# WiFi_Turntable_Controller_v2.net
KiCad netlist of a schematic drawn in EAGLE
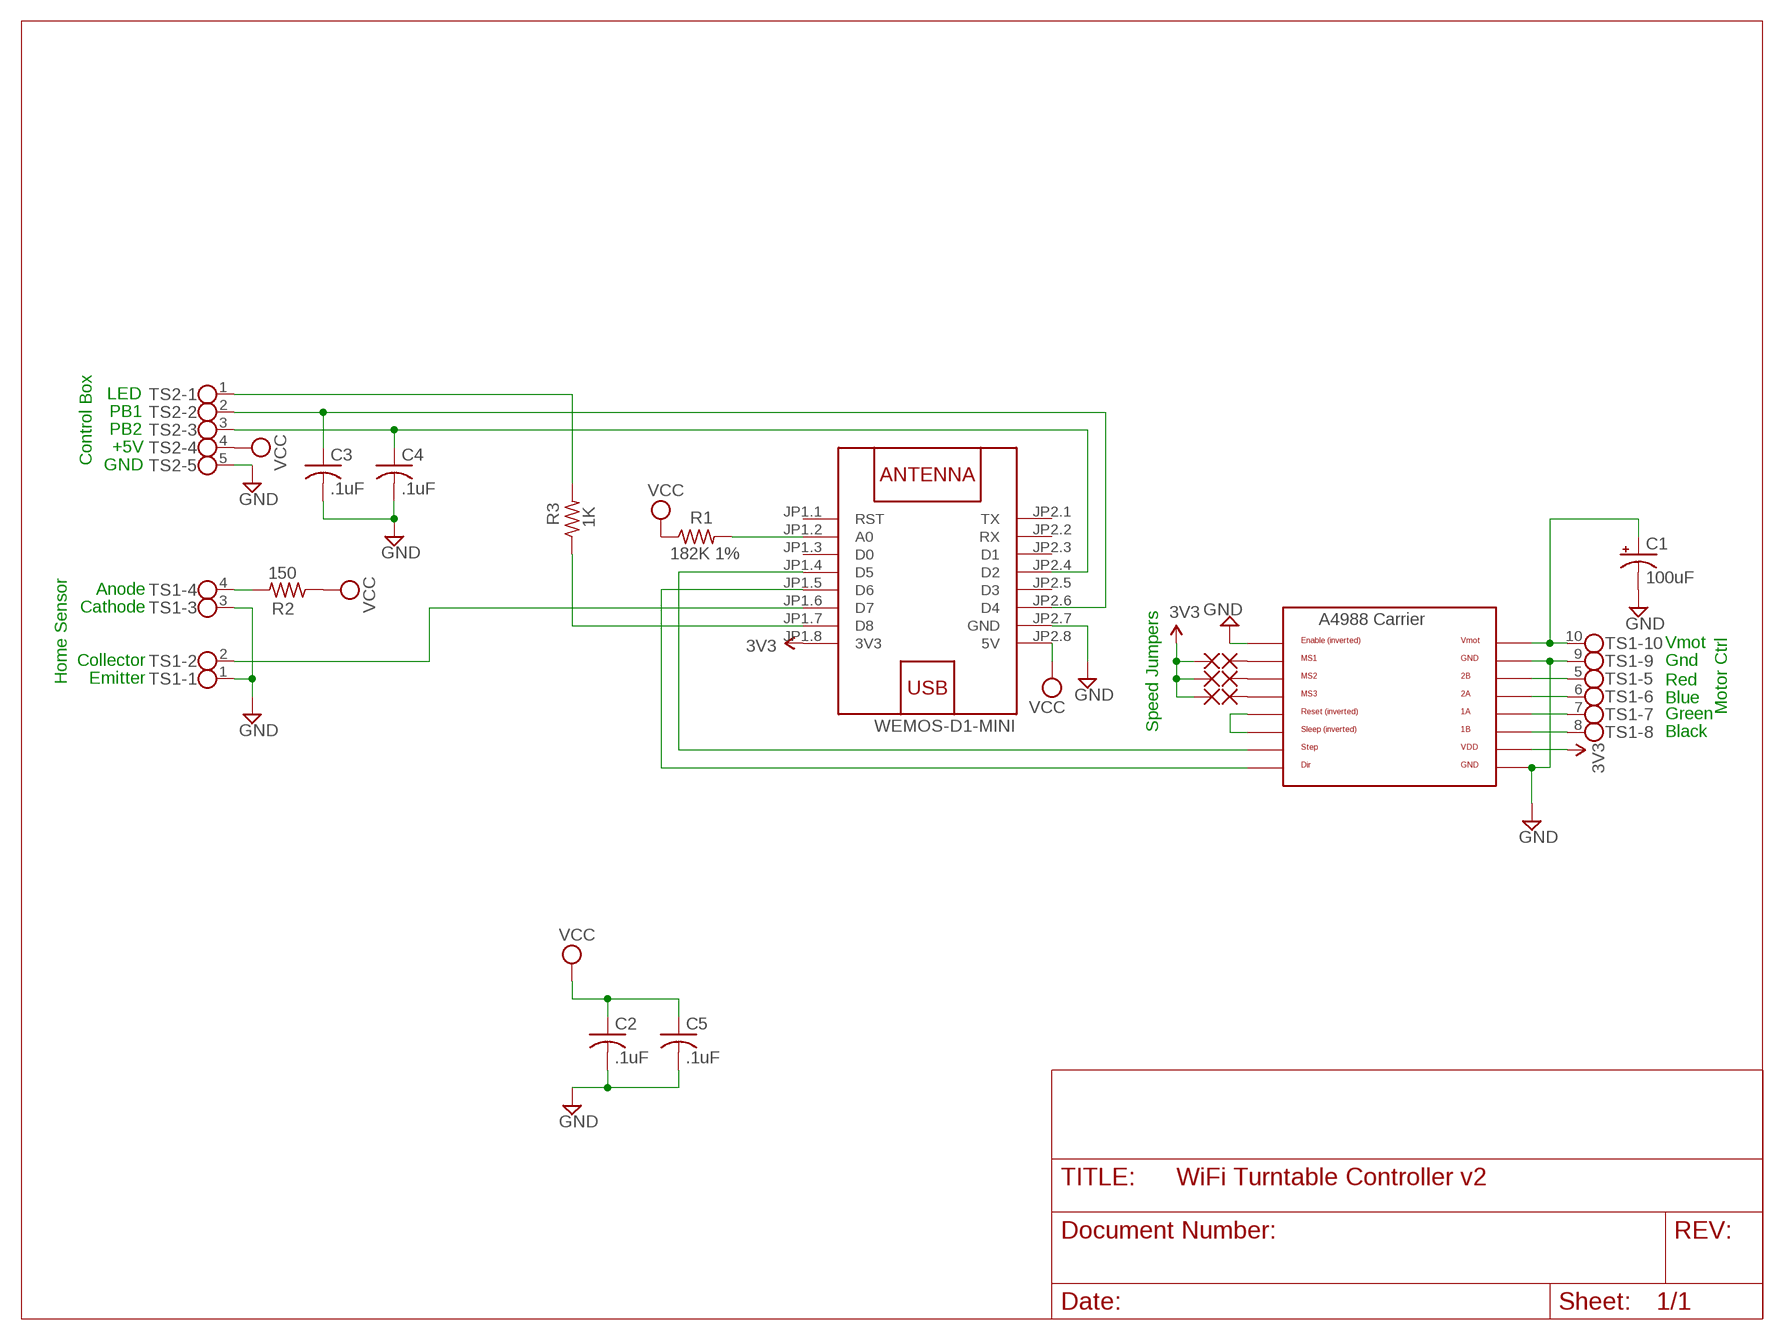
[diagram p0: schematic, sheet 1]

(export (version "E")
  (design (tool "Eeschema 10.0.6"))
  (components
    (comp (ref "C1")
      (value "100uF")
      (footprint "eagle-import:E3,5-8")
      (libsource (lib "eagle-import") (part "CPOL-USE3.5-8"))
    )
    (comp (ref "C2")
      (value ".1uF")
      (footprint "eagle-import:C1206")
      (libsource (lib "eagle-import") (part "C-USC1206"))
    )
    (comp (ref "C3")
      (value ".1uF")
      (footprint "eagle-import:C1206")
      (libsource (lib "eagle-import") (part "C-USC1206"))
    )
    (comp (ref "C4")
      (value ".1uF")
      (footprint "eagle-import:C1206")
      (libsource (lib "eagle-import") (part "C-USC1206"))
    )
    (comp (ref "C5")
      (value ".1uF")
      (footprint "eagle-import:C1206")
      (libsource (lib "eagle-import") (part "C-USC1206"))
    )
    (comp (ref "PAD1")
      (value "1,6/0,8")
      (footprint "eagle-import:1,6_0,8")
      (libsource (lib "eagle-import") (part "1,6/0,8"))
    )
    (comp (ref "PAD2")
      (value "1,6/0,8")
      (footprint "eagle-import:1,6_0,8")
      (libsource (lib "eagle-import") (part "1,6/0,8"))
    )
    (comp (ref "PAD3")
      (value "1,6/0,8")
      (footprint "eagle-import:1,6_0,8")
      (libsource (lib "eagle-import") (part "1,6/0,8"))
    )
    (comp (ref "PAD4")
      (value "1,6/0,8")
      (footprint "eagle-import:1,6_0,8")
      (libsource (lib "eagle-import") (part "1,6/0,8"))
    )
    (comp (ref "PAD5")
      (value "1,6/0,8")
      (footprint "eagle-import:1,6_0,8")
      (libsource (lib "eagle-import") (part "1,6/0,8"))
    )
    (comp (ref "PAD6")
      (value "1,6/0,8")
      (footprint "eagle-import:1,6_0,8")
      (libsource (lib "eagle-import") (part "1,6/0,8"))
    )
    (comp (ref "R1")
      (value "182K 1%")
      (footprint "eagle-import:R1206")
      (libsource (lib "eagle-import") (part "R-US_R1206"))
    )
    (comp (ref "R2")
      (value "150")
      (footprint "eagle-import:R1206")
      (libsource (lib "eagle-import") (part "R-US_R1206"))
    )
    (comp (ref "R3")
      (value "1K")
      (footprint "eagle-import:R1206")
      (libsource (lib "eagle-import") (part "R-US_R1206"))
    )
    (comp (ref "TS1")
      (value "TERMBLK10")
      (footprint "eagle-import:10PB")
      (libsource (lib "eagle-import") (part "TERMBLK10"))
    )
    (comp (ref "TS2")
      (value "TERMBLK05")
      (footprint "eagle-import:05PB")
      (libsource (lib "eagle-import") (part "TERMBLK05"))
    )
    (comp (ref "U$1")
      (value "WEMOS-D1-MINI")
      (footprint "eagle-import:WEMOS-D1-MINI")
      (libsource (lib "eagle-import") (part "WEMOS-D1-MINI"))
    )
    (comp (ref "U$2")
      (value "A4988BREAKOUT")
      (footprint "eagle-import:A4988BREAKOUT")
      (libsource (lib "eagle-import") (part "A4988BREAKOUT"))
    )
  )
  (nets
    (net (code "1") (name "3V3") (class "Default")
      (node (ref "PAD4") (pin "1") (pinfunction "P_1") (pintype "passive"))
      (node (ref "PAD5") (pin "1") (pinfunction "P_1") (pintype "passive"))
      (node (ref "PAD6") (pin "1") (pinfunction "P_1") (pintype "passive"))
      (node (ref "U$1") (pin "JP1.8") (pinfunction "3V3_JP1.8") (pintype "power_in"))
      (node (ref "U$2") (pin "VDD") (pinfunction "VDD_VDD") (pintype "power_in"))
    )
    (net (code "2") (name "GND") (class "Default")
      (node (ref "C1") (pin "-") (pinfunction "-_-") (pintype "passive"))
      (node (ref "C2") (pin "2") (pinfunction "2_2") (pintype "passive"))
      (node (ref "C3") (pin "2") (pinfunction "2_2") (pintype "passive"))
      (node (ref "C4") (pin "2") (pinfunction "2_2") (pintype "passive"))
      (node (ref "C5") (pin "2") (pinfunction "2_2") (pintype "passive"))
      (node (ref "TS1") (pin "1") (pinfunction "1_1") (pintype "passive"))
      (node (ref "TS1") (pin "3") (pinfunction "1_3") (pintype "passive"))
      (node (ref "TS1") (pin "9") (pinfunction "1_9") (pintype "passive"))
      (node (ref "TS2") (pin "5") (pinfunction "1_5") (pintype "passive"))
      (node (ref "U$1") (pin "JP2.7") (pinfunction "GND_JP2.7") (pintype "power_in"))
      (node (ref "U$2") (pin "EN") (pinfunction "EN_EN") (pintype "input"))
      (node (ref "U$2") (pin "GND") (pinfunction "GND_GND") (pintype "power_in"))
      (node (ref "U$2") (pin "GND@0") (pinfunction "GND_GND@0") (pintype "power_in"))
    )
    (net (code "3") (name "Net-(PAD1-P)") (class "Default")
      (node (ref "PAD1") (pin "1") (pinfunction "P_1") (pintype "passive"))
      (node (ref "U$2") (pin "MS1") (pinfunction "MS1_MS1") (pintype "input"))
    )
    (net (code "4") (name "Net-(PAD2-P)") (class "Default")
      (node (ref "PAD2") (pin "1") (pinfunction "P_1") (pintype "passive"))
      (node (ref "U$2") (pin "MS2") (pinfunction "MS2_MS2") (pintype "input"))
    )
    (net (code "5") (name "Net-(PAD3-P)") (class "Default")
      (node (ref "PAD3") (pin "1") (pinfunction "P_1") (pintype "passive"))
      (node (ref "U$2") (pin "MS3") (pinfunction "MS3_MS3") (pintype "input"))
    )
    (net (code "6") (name "Net-(R3-Pad2)") (class "Default")
      (node (ref "R3") (pin "2") (pinfunction "2_2") (pintype "passive"))
      (node (ref "TS2") (pin "1") (pinfunction "1_1") (pintype "passive"))
    )
    (net (code "7") (name "Net-(TS1B-1)") (class "Default")
      (node (ref "C1") (pin "+") (pinfunction "+_+") (pintype "passive"))
      (node (ref "TS1") (pin "10") (pinfunction "1_10") (pintype "passive"))
      (node (ref "U$2") (pin "VMOT") (pinfunction "VMOT_VMOT") (pintype "power_in"))
    )
    (net (code "8") (name "Net-(TS1C-1)") (class "Default")
      (node (ref "TS1") (pin "2") (pinfunction "1_2") (pintype "passive"))
      (node (ref "U$1") (pin "JP1.6") (pinfunction "D7_JP1.6") (pintype "bidirectional"))
    )
    (net (code "9") (name "Net-(TS1E-1)") (class "Default")
      (node (ref "R2") (pin "2") (pinfunction "2_2") (pintype "passive"))
      (node (ref "TS1") (pin "4") (pinfunction "1_4") (pintype "passive"))
    )
    (net (code "10") (name "Net-(TS1F-1)") (class "Default")
      (node (ref "TS1") (pin "5") (pinfunction "1_5") (pintype "passive"))
      (node (ref "U$2") (pin "2B") (pinfunction "2B_2B") (pintype "output"))
    )
    (net (code "11") (name "Net-(TS1G-1)") (class "Default")
      (node (ref "TS1") (pin "6") (pinfunction "1_6") (pintype "passive"))
      (node (ref "U$2") (pin "2A") (pinfunction "2A_2A") (pintype "output"))
    )
    (net (code "12") (name "Net-(TS1H-1)") (class "Default")
      (node (ref "TS1") (pin "7") (pinfunction "1_7") (pintype "passive"))
      (node (ref "U$2") (pin "1A") (pinfunction "1A_1A") (pintype "output"))
    )
    (net (code "13") (name "Net-(TS1I-1)") (class "Default")
      (node (ref "TS1") (pin "8") (pinfunction "1_8") (pintype "passive"))
      (node (ref "U$2") (pin "1B") (pinfunction "1B_1B") (pintype "output"))
    )
    (net (code "14") (name "Net-(TS2B-1)") (class "Default")
      (node (ref "C3") (pin "1") (pinfunction "1_1") (pintype "passive"))
      (node (ref "TS2") (pin "2") (pinfunction "1_2") (pintype "passive"))
      (node (ref "U$1") (pin "JP2.6") (pinfunction "D4_JP2.6") (pintype "bidirectional"))
    )
    (net (code "15") (name "Net-(TS2C-1)") (class "Default")
      (node (ref "C4") (pin "1") (pinfunction "1_1") (pintype "passive"))
      (node (ref "TS2") (pin "3") (pinfunction "1_3") (pintype "passive"))
      (node (ref "U$1") (pin "JP2.4") (pinfunction "D2_JP2.4") (pintype "bidirectional"))
    )
    (net (code "16") (name "Net-(U$1-A0)") (class "Default")
      (node (ref "R1") (pin "2") (pinfunction "2_2") (pintype "passive"))
      (node (ref "U$1") (pin "JP1.2") (pinfunction "A0_JP1.2") (pintype "bidirectional"))
    )
    (net (code "17") (name "Net-(U$1-D5)") (class "Default")
      (node (ref "U$1") (pin "JP1.4") (pinfunction "D5_JP1.4") (pintype "bidirectional"))
      (node (ref "U$2") (pin "STEP") (pinfunction "STEP_STEP") (pintype "input"))
    )
    (net (code "18") (name "Net-(U$1-D6)") (class "Default")
      (node (ref "U$1") (pin "JP1.5") (pinfunction "D6_JP1.5") (pintype "bidirectional"))
      (node (ref "U$2") (pin "DIR") (pinfunction "DIR_DIR") (pintype "input"))
    )
    (net (code "19") (name "Net-(U$1-D8)") (class "Default")
      (node (ref "R3") (pin "1") (pinfunction "1_1") (pintype "passive"))
      (node (ref "U$1") (pin "JP1.7") (pinfunction "D8_JP1.7") (pintype "bidirectional"))
    )
    (net (code "20") (name "Net-(U$2-SLEEP)") (class "Default")
      (node (ref "U$2") (pin "RST") (pinfunction "RST_RST") (pintype "input"))
      (node (ref "U$2") (pin "SLP") (pinfunction "SLEEP_SLP") (pintype "input"))
    )
    (net (code "21") (name "VCC") (class "Default")
      (node (ref "C2") (pin "1") (pinfunction "1_1") (pintype "passive"))
      (node (ref "C5") (pin "1") (pinfunction "1_1") (pintype "passive"))
      (node (ref "R1") (pin "1") (pinfunction "1_1") (pintype "passive"))
      (node (ref "R2") (pin "1") (pinfunction "1_1") (pintype "passive"))
      (node (ref "TS2") (pin "4") (pinfunction "1_4") (pintype "passive"))
      (node (ref "U$1") (pin "JP2.8") (pinfunction "5V_JP2.8") (pintype "power_in"))
    )
    (net (code "22") (name "unconnected-(U$1-D0-PadJP1.3)") (class "Default")
      (node (ref "U$1") (pin "JP1.3") (pinfunction "D0_JP1.3") (pintype "bidirectional"))
    )
    (net (code "23") (name "unconnected-(U$1-D1-PadJP2.3)") (class "Default")
      (node (ref "U$1") (pin "JP2.3") (pinfunction "D1_JP2.3") (pintype "bidirectional"))
    )
    (net (code "24") (name "unconnected-(U$1-D3-PadJP2.5)") (class "Default")
      (node (ref "U$1") (pin "JP2.5") (pinfunction "D3_JP2.5") (pintype "bidirectional"))
    )
    (net (code "25") (name "unconnected-(U$1-RST-PadJP1.1)") (class "Default")
      (node (ref "U$1") (pin "JP1.1") (pinfunction "RST_JP1.1") (pintype "bidirectional"))
    )
    (net (code "26") (name "unconnected-(U$1-RX-PadJP2.2)") (class "Default")
      (node (ref "U$1") (pin "JP2.2") (pinfunction "RX_JP2.2") (pintype "bidirectional"))
    )
    (net (code "27") (name "unconnected-(U$1-TX-PadJP2.1)") (class "Default")
      (node (ref "U$1") (pin "JP2.1") (pinfunction "TX_JP2.1") (pintype "bidirectional"))
    )
  )
)
